# NanoLoRaBreakout_2019-05-14.net
KiCad netlist of a schematic drawn in EAGLE
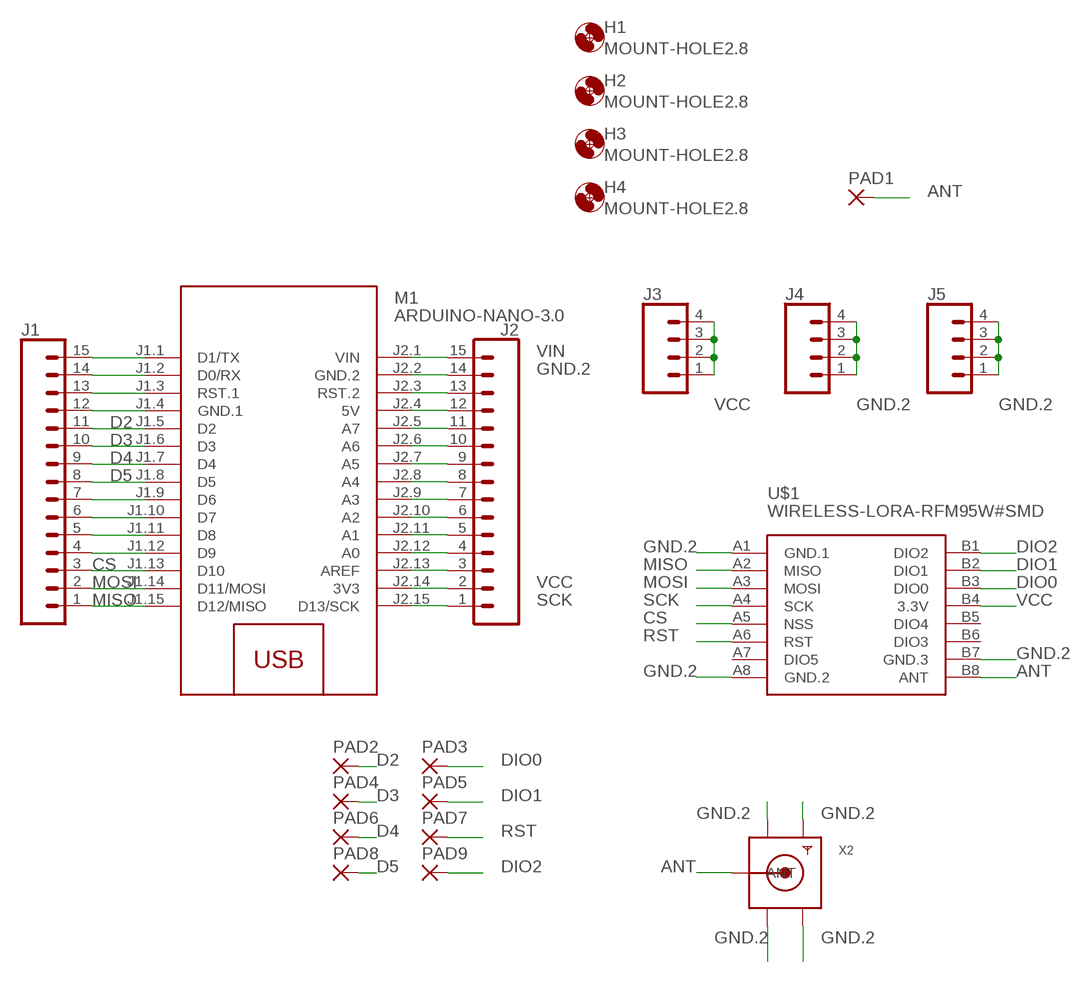
[diagram p0: schematic, sheet 1]

(export (version "E")
  (design (tool "Eeschema 10.0.6"))
  (components
    (comp (ref "H1")
      (value "MOUNT-HOLE2.8")
      (footprint "eagle-import:2,8")
      (libsource (lib "eagle-import") (part "MOUNT-HOLE2.8"))
    )
    (comp (ref "H2")
      (value "MOUNT-HOLE2.8")
      (footprint "eagle-import:2,8")
      (libsource (lib "eagle-import") (part "MOUNT-HOLE2.8"))
    )
    (comp (ref "H3")
      (value "MOUNT-HOLE2.8")
      (footprint "eagle-import:2,8")
      (libsource (lib "eagle-import") (part "MOUNT-HOLE2.8"))
    )
    (comp (ref "H4")
      (value "MOUNT-HOLE2.8")
      (footprint "eagle-import:2,8")
      (libsource (lib "eagle-import") (part "MOUNT-HOLE2.8"))
    )
    (comp (ref "J1")
      (value "CONN_15")
      (footprint "eagle-import:1X15")
      (libsource (lib "eagle-import") (part "CONN_15"))
    )
    (comp (ref "J2")
      (value "CONN_15")
      (footprint "eagle-import:1X15")
      (libsource (lib "eagle-import") (part "CONN_15"))
    )
    (comp (ref "J3")
      (value "CONN_04")
      (footprint "eagle-import:1X04")
      (libsource (lib "eagle-import") (part "CONN_04"))
    )
    (comp (ref "J4")
      (value "CONN_04")
      (footprint "eagle-import:1X04")
      (libsource (lib "eagle-import") (part "CONN_04"))
    )
    (comp (ref "J5")
      (value "CONN_04")
      (footprint "eagle-import:1X04")
      (libsource (lib "eagle-import") (part "CONN_04"))
    )
    (comp (ref "M1")
      (value "ARDUINO-NANO-3.0")
      (footprint "eagle-import:ARDUINO-NANO-3.0")
      (libsource (lib "eagle-import") (part "ARDUINO-NANO-3.0"))
    )
    (comp (ref "PAD1")
      (value "1,6/0,8")
      (footprint "eagle-import:1,6_0,8")
      (libsource (lib "eagle-import") (part "1,6/0,8"))
    )
    (comp (ref "PAD2")
      (value "SMD2")
      (footprint "eagle-import:SMD1,27-2,54")
      (libsource (lib "eagle-import") (part "SMD2"))
    )
    (comp (ref "PAD3")
      (value "SMD2")
      (footprint "eagle-import:SMD1,27-2,54")
      (libsource (lib "eagle-import") (part "SMD2"))
    )
    (comp (ref "PAD4")
      (value "SMD2")
      (footprint "eagle-import:SMD1,27-2,54")
      (libsource (lib "eagle-import") (part "SMD2"))
    )
    (comp (ref "PAD5")
      (value "SMD2")
      (footprint "eagle-import:SMD1,27-2,54")
      (libsource (lib "eagle-import") (part "SMD2"))
    )
    (comp (ref "PAD6")
      (value "SMD2")
      (footprint "eagle-import:SMD1,27-2,54")
      (libsource (lib "eagle-import") (part "SMD2"))
    )
    (comp (ref "PAD7")
      (value "SMD2")
      (footprint "eagle-import:SMD1,27-2,54")
      (libsource (lib "eagle-import") (part "SMD2"))
    )
    (comp (ref "PAD8")
      (value "SMD2")
      (footprint "eagle-import:SMD1,27-2,54")
      (libsource (lib "eagle-import") (part "SMD2"))
    )
    (comp (ref "PAD9")
      (value "SMD2")
      (footprint "eagle-import:SMD1,27-2,54")
      (libsource (lib "eagle-import") (part "SMD2"))
    )
    (comp (ref "U$1")
      (value "WIRELESS-LORA-RFM95W#SMD")
      (footprint "eagle-import:WIRELESS-LORA-RFM95W#SMD")
      (libsource (lib "eagle-import") (part "WIRELESS-LORA-RFM95W#SMD"))
    )
    (comp (ref "X2")
      (value "SMACONNECTOR_EDGE_UFL")
      (footprint "eagle-import:SMA_EDGELAUNCH_UFL")
      (libsource (lib "eagle-import") (part "SMACONNECTOR_EDGE_UFL"))
    )
  )
  (nets
    (net (code "1") (name "/ANT") (class "Default")
      (node (ref "PAD1") (pin "1") (pinfunction "P_1") (pintype "passive"))
      (node (ref "U$1") (pin "B8") (pinfunction "ANT_B8") (pintype "passive"))
      (node (ref "X2") (pin "P") (pinfunction "ANT_P") (pintype "bidirectional"))
    )
    (net (code "2") (name "/CS") (class "Default")
      (node (ref "J1") (pin "3") (pinfunction "3_3") (pintype "passive"))
      (node (ref "M1") (pin "J1.13") (pinfunction "D10_J1.13") (pintype "bidirectional"))
      (node (ref "U$1") (pin "A5") (pinfunction "NSS_A5") (pintype "bidirectional"))
    )
    (net (code "3") (name "/D2") (class "Default")
      (node (ref "J1") (pin "11") (pinfunction "11_11") (pintype "passive"))
      (node (ref "M1") (pin "J1.5") (pinfunction "D2_J1.5") (pintype "bidirectional"))
      (node (ref "PAD2") (pin "1") (pinfunction "P_1") (pintype "passive"))
    )
    (net (code "4") (name "/D3") (class "Default")
      (node (ref "J1") (pin "10") (pinfunction "10_10") (pintype "passive"))
      (node (ref "M1") (pin "J1.6") (pinfunction "D3_J1.6") (pintype "bidirectional"))
      (node (ref "PAD4") (pin "1") (pinfunction "P_1") (pintype "passive"))
    )
    (net (code "5") (name "/D4") (class "Default")
      (node (ref "J1") (pin "9") (pinfunction "9_9") (pintype "passive"))
      (node (ref "M1") (pin "J1.7") (pinfunction "D4_J1.7") (pintype "bidirectional"))
      (node (ref "PAD6") (pin "1") (pinfunction "P_1") (pintype "passive"))
    )
    (net (code "6") (name "/D5") (class "Default")
      (node (ref "J1") (pin "8") (pinfunction "8_8") (pintype "passive"))
      (node (ref "M1") (pin "J1.8") (pinfunction "D5_J1.8") (pintype "bidirectional"))
      (node (ref "PAD8") (pin "1") (pinfunction "P_1") (pintype "passive"))
    )
    (net (code "7") (name "/DIO0") (class "Default")
      (node (ref "PAD3") (pin "1") (pinfunction "P_1") (pintype "passive"))
      (node (ref "U$1") (pin "B3") (pinfunction "DIO0_B3") (pintype "bidirectional"))
    )
    (net (code "8") (name "/DIO1") (class "Default")
      (node (ref "PAD5") (pin "1") (pinfunction "P_1") (pintype "passive"))
      (node (ref "U$1") (pin "B2") (pinfunction "DIO1_B2") (pintype "bidirectional"))
    )
    (net (code "9") (name "/DIO2") (class "Default")
      (node (ref "PAD9") (pin "1") (pinfunction "P_1") (pintype "passive"))
      (node (ref "U$1") (pin "B1") (pinfunction "DIO2_B1") (pintype "bidirectional"))
    )
    (net (code "10") (name "/GND.2") (class "Default")
      (node (ref "J2") (pin "14") (pinfunction "14_14") (pintype "passive"))
      (node (ref "J4") (pin "1") (pinfunction "1_1") (pintype "passive"))
      (node (ref "J4") (pin "2") (pinfunction "2_2") (pintype "passive"))
      (node (ref "J4") (pin "3") (pinfunction "3_3") (pintype "passive"))
      (node (ref "J4") (pin "4") (pinfunction "4_4") (pintype "passive"))
      (node (ref "J5") (pin "1") (pinfunction "1_1") (pintype "passive"))
      (node (ref "J5") (pin "2") (pinfunction "2_2") (pintype "passive"))
      (node (ref "J5") (pin "3") (pinfunction "3_3") (pintype "passive"))
      (node (ref "J5") (pin "4") (pinfunction "4_4") (pintype "passive"))
      (node (ref "M1") (pin "J2.2") (pinfunction "GND.2_J2.2") (pintype "power_in"))
      (node (ref "U$1") (pin "A1") (pinfunction "GND.1_A1") (pintype "power_in"))
      (node (ref "U$1") (pin "A8") (pinfunction "GND.2_A8") (pintype "power_in"))
      (node (ref "U$1") (pin "B7") (pinfunction "GND.3_B7") (pintype "power_in"))
      (node (ref "X2") (pin "GND@1") (pinfunction "GND1_GND@1") (pintype "power_in"))
      (node (ref "X2") (pin "GND@2") (pinfunction "GND2_GND@2") (pintype "power_in"))
      (node (ref "X2") (pin "GND@3") (pinfunction "GND3_GND@3") (pintype "power_in"))
      (node (ref "X2") (pin "GND@4") (pinfunction "GND4_GND@4") (pintype "power_in"))
    )
    (net (code "11") (name "/MISO") (class "Default")
      (node (ref "J1") (pin "1") (pinfunction "1_1") (pintype "passive"))
      (node (ref "M1") (pin "J1.15") (pinfunction "D12/MISO_J1.15") (pintype "bidirectional"))
      (node (ref "U$1") (pin "A2") (pinfunction "MISO_A2") (pintype "bidirectional"))
    )
    (net (code "12") (name "/MOSI") (class "Default")
      (node (ref "J1") (pin "2") (pinfunction "2_2") (pintype "passive"))
      (node (ref "M1") (pin "J1.14") (pinfunction "D11/MOSI_J1.14") (pintype "bidirectional"))
      (node (ref "U$1") (pin "A3") (pinfunction "MOSI_A3") (pintype "bidirectional"))
    )
    (net (code "13") (name "/RST") (class "Default")
      (node (ref "PAD7") (pin "1") (pinfunction "P_1") (pintype "passive"))
      (node (ref "U$1") (pin "A6") (pinfunction "RST_A6") (pintype "bidirectional"))
    )
    (net (code "14") (name "/SCK") (class "Default")
      (node (ref "J2") (pin "1") (pinfunction "1_1") (pintype "passive"))
      (node (ref "M1") (pin "J2.15") (pinfunction "D13/SCK_J2.15") (pintype "bidirectional"))
      (node (ref "U$1") (pin "A4") (pinfunction "SCK_A4") (pintype "bidirectional"))
    )
    (net (code "15") (name "/VCC") (class "Default")
      (node (ref "J2") (pin "2") (pinfunction "2_2") (pintype "passive"))
      (node (ref "J3") (pin "1") (pinfunction "1_1") (pintype "passive"))
      (node (ref "J3") (pin "2") (pinfunction "2_2") (pintype "passive"))
      (node (ref "J3") (pin "3") (pinfunction "3_3") (pintype "passive"))
      (node (ref "J3") (pin "4") (pinfunction "4_4") (pintype "passive"))
      (node (ref "M1") (pin "J2.14") (pinfunction "3V3_J2.14") (pintype "power_in"))
      (node (ref "U$1") (pin "B4") (pinfunction "3.3V_B4") (pintype "power_in"))
    )
    (net (code "16") (name "/VIN") (class "Default")
      (node (ref "J2") (pin "15") (pinfunction "15_15") (pintype "passive"))
      (node (ref "M1") (pin "J2.1") (pinfunction "VIN_J2.1") (pintype "power_in"))
    )
    (net (code "17") (name "Net-(M1-5V)") (class "Default")
      (node (ref "J2") (pin "12") (pinfunction "12_12") (pintype "passive"))
      (node (ref "M1") (pin "J2.4") (pinfunction "5V_J2.4") (pintype "power_in"))
    )
    (net (code "18") (name "Net-(M1-A0)") (class "Default")
      (node (ref "J2") (pin "4") (pinfunction "4_4") (pintype "passive"))
      (node (ref "M1") (pin "J2.12") (pinfunction "A0_J2.12") (pintype "bidirectional"))
    )
    (net (code "19") (name "Net-(M1-A1)") (class "Default")
      (node (ref "J2") (pin "5") (pinfunction "5_5") (pintype "passive"))
      (node (ref "M1") (pin "J2.11") (pinfunction "A1_J2.11") (pintype "bidirectional"))
    )
    (net (code "20") (name "Net-(M1-A2)") (class "Default")
      (node (ref "J2") (pin "6") (pinfunction "6_6") (pintype "passive"))
      (node (ref "M1") (pin "J2.10") (pinfunction "A2_J2.10") (pintype "bidirectional"))
    )
    (net (code "21") (name "Net-(M1-A3)") (class "Default")
      (node (ref "J2") (pin "7") (pinfunction "7_7") (pintype "passive"))
      (node (ref "M1") (pin "J2.9") (pinfunction "A3_J2.9") (pintype "bidirectional"))
    )
    (net (code "22") (name "Net-(M1-A4)") (class "Default")
      (node (ref "J2") (pin "8") (pinfunction "8_8") (pintype "passive"))
      (node (ref "M1") (pin "J2.8") (pinfunction "A4_J2.8") (pintype "bidirectional"))
    )
    (net (code "23") (name "Net-(M1-A5)") (class "Default")
      (node (ref "J2") (pin "9") (pinfunction "9_9") (pintype "passive"))
      (node (ref "M1") (pin "J2.7") (pinfunction "A5_J2.7") (pintype "bidirectional"))
    )
    (net (code "24") (name "Net-(M1-A6)") (class "Default")
      (node (ref "J2") (pin "10") (pinfunction "10_10") (pintype "passive"))
      (node (ref "M1") (pin "J2.6") (pinfunction "A6_J2.6") (pintype "bidirectional"))
    )
    (net (code "25") (name "Net-(M1-A7)") (class "Default")
      (node (ref "J2") (pin "11") (pinfunction "11_11") (pintype "passive"))
      (node (ref "M1") (pin "J2.5") (pinfunction "A7_J2.5") (pintype "bidirectional"))
    )
    (net (code "26") (name "Net-(M1-AREF)") (class "Default")
      (node (ref "J2") (pin "3") (pinfunction "3_3") (pintype "passive"))
      (node (ref "M1") (pin "J2.13") (pinfunction "AREF_J2.13") (pintype "bidirectional"))
    )
    (net (code "27") (name "Net-(M1-D0{slash}RX)") (class "Default")
      (node (ref "J1") (pin "14") (pinfunction "14_14") (pintype "passive"))
      (node (ref "M1") (pin "J1.2") (pinfunction "D0/RX_J1.2") (pintype "bidirectional"))
    )
    (net (code "28") (name "Net-(M1-D1{slash}TX)") (class "Default")
      (node (ref "J1") (pin "15") (pinfunction "15_15") (pintype "passive"))
      (node (ref "M1") (pin "J1.1") (pinfunction "D1/TX_J1.1") (pintype "bidirectional"))
    )
    (net (code "29") (name "Net-(M1-D6)") (class "Default")
      (node (ref "J1") (pin "7") (pinfunction "7_7") (pintype "passive"))
      (node (ref "M1") (pin "J1.9") (pinfunction "D6_J1.9") (pintype "bidirectional"))
    )
    (net (code "30") (name "Net-(M1-D7)") (class "Default")
      (node (ref "J1") (pin "6") (pinfunction "6_6") (pintype "passive"))
      (node (ref "M1") (pin "J1.10") (pinfunction "D7_J1.10") (pintype "bidirectional"))
    )
    (net (code "31") (name "Net-(M1-D8)") (class "Default")
      (node (ref "J1") (pin "5") (pinfunction "5_5") (pintype "passive"))
      (node (ref "M1") (pin "J1.11") (pinfunction "D8_J1.11") (pintype "bidirectional"))
    )
    (net (code "32") (name "Net-(M1-D9)") (class "Default")
      (node (ref "J1") (pin "4") (pinfunction "4_4") (pintype "passive"))
      (node (ref "M1") (pin "J1.12") (pinfunction "D9_J1.12") (pintype "bidirectional"))
    )
    (net (code "33") (name "Net-(M1-GND.1)") (class "Default")
      (node (ref "J1") (pin "12") (pinfunction "12_12") (pintype "passive"))
      (node (ref "M1") (pin "J1.4") (pinfunction "GND.1_J1.4") (pintype "power_in"))
    )
    (net (code "34") (name "Net-(M1-RST.1)") (class "Default")
      (node (ref "J1") (pin "13") (pinfunction "13_13") (pintype "passive"))
      (node (ref "M1") (pin "J1.3") (pinfunction "RST.1_J1.3") (pintype "bidirectional"))
    )
    (net (code "35") (name "Net-(M1-RST.2)") (class "Default")
      (node (ref "J2") (pin "13") (pinfunction "13_13") (pintype "passive"))
      (node (ref "M1") (pin "J2.3") (pinfunction "RST.2_J2.3") (pintype "bidirectional"))
    )
    (net (code "36") (name "unconnected-(U$1-DIO3-PadB6)") (class "Default")
      (node (ref "U$1") (pin "B6") (pinfunction "DIO3_B6") (pintype "bidirectional"))
    )
    (net (code "37") (name "unconnected-(U$1-DIO4-PadB5)") (class "Default")
      (node (ref "U$1") (pin "B5") (pinfunction "DIO4_B5") (pintype "bidirectional"))
    )
    (net (code "38") (name "unconnected-(U$1-DIO5-PadA7)") (class "Default")
      (node (ref "U$1") (pin "A7") (pinfunction "DIO5_A7") (pintype "bidirectional"))
    )
  )
)
